# replay_adapter.net
KiCad netlist of a schematic drawn in EAGLE
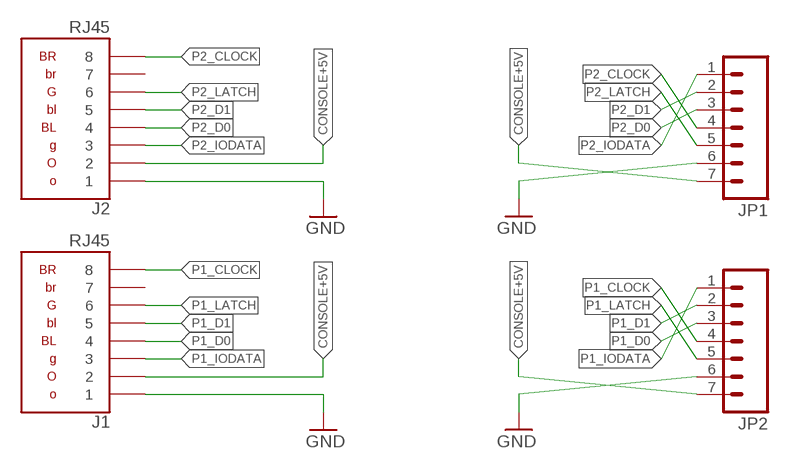
[diagram p0: schematic, sheet 1]

(export (version "E")
  (design (tool "Eeschema 10.0.6"))
  (components
    (comp (ref "J1")
      (value "RJ45")
      (footprint "eagle-import:RJ45")
      (libsource (lib "eagle-import") (part "RJ45"))
    )
    (comp (ref "J2")
      (value "RJ45")
      (footprint "eagle-import:RJ45")
      (libsource (lib "eagle-import") (part "RJ45"))
    )
    (comp (ref "JP1")
      (value "M07")
      (footprint "eagle-import:1X07")
      (libsource (lib "eagle-import") (part "M07"))
    )
    (comp (ref "JP2")
      (value "M07")
      (footprint "eagle-import:1X07")
      (libsource (lib "eagle-import") (part "M07"))
    )
  )
  (nets
    (net (code "1") (name "CONSOLE+5V") (class "Default")
      (node (ref "J1") (pin "2") (pinfunction "2_2") (pintype "bidirectional"))
      (node (ref "J2") (pin "2") (pinfunction "2_2") (pintype "bidirectional"))
      (node (ref "JP1") (pin "7") (pinfunction "7_7") (pintype "passive"))
      (node (ref "JP2") (pin "7") (pinfunction "7_7") (pintype "passive"))
    )
    (net (code "2") (name "GND") (class "Default")
      (node (ref "J1") (pin "1") (pinfunction "1_1") (pintype "bidirectional"))
      (node (ref "J2") (pin "1") (pinfunction "1_1") (pintype "bidirectional"))
      (node (ref "JP1") (pin "6") (pinfunction "6_6") (pintype "passive"))
      (node (ref "JP2") (pin "6") (pinfunction "6_6") (pintype "passive"))
    )
    (net (code "3") (name "P1_CLOCK") (class "Default")
      (node (ref "J1") (pin "8") (pinfunction "8_8") (pintype "bidirectional"))
      (node (ref "JP2") (pin "4") (pinfunction "4_4") (pintype "passive"))
    )
    (net (code "4") (name "P1_D0") (class "Default")
      (node (ref "J1") (pin "4") (pinfunction "4_4") (pintype "bidirectional"))
      (node (ref "JP2") (pin "3") (pinfunction "3_3") (pintype "passive"))
    )
    (net (code "5") (name "P1_D1") (class "Default")
      (node (ref "J1") (pin "5") (pinfunction "5_5") (pintype "bidirectional"))
      (node (ref "JP2") (pin "2") (pinfunction "2_2") (pintype "passive"))
    )
    (net (code "6") (name "P1_IODATA") (class "Default")
      (node (ref "J1") (pin "3") (pinfunction "3_3") (pintype "bidirectional"))
      (node (ref "JP2") (pin "1") (pinfunction "1_1") (pintype "passive"))
    )
    (net (code "7") (name "P1_LATCH") (class "Default")
      (node (ref "J1") (pin "6") (pinfunction "6_6") (pintype "bidirectional"))
      (node (ref "JP2") (pin "5") (pinfunction "5_5") (pintype "passive"))
    )
    (net (code "8") (name "P2_CLOCK") (class "Default")
      (node (ref "J2") (pin "8") (pinfunction "8_8") (pintype "bidirectional"))
      (node (ref "JP1") (pin "4") (pinfunction "4_4") (pintype "passive"))
    )
    (net (code "9") (name "P2_D0") (class "Default")
      (node (ref "J2") (pin "4") (pinfunction "4_4") (pintype "bidirectional"))
      (node (ref "JP1") (pin "3") (pinfunction "3_3") (pintype "passive"))
    )
    (net (code "10") (name "P2_D1") (class "Default")
      (node (ref "J2") (pin "5") (pinfunction "5_5") (pintype "bidirectional"))
      (node (ref "JP1") (pin "2") (pinfunction "2_2") (pintype "passive"))
    )
    (net (code "11") (name "P2_IODATA") (class "Default")
      (node (ref "J2") (pin "3") (pinfunction "3_3") (pintype "bidirectional"))
      (node (ref "JP1") (pin "1") (pinfunction "1_1") (pintype "passive"))
    )
    (net (code "12") (name "P2_LATCH") (class "Default")
      (node (ref "J2") (pin "6") (pinfunction "6_6") (pintype "bidirectional"))
      (node (ref "JP1") (pin "5") (pinfunction "5_5") (pintype "passive"))
    )
    (net (code "13") (name "unconnected-(J1-Pad7)") (class "Default")
      (node (ref "J1") (pin "7") (pinfunction "7_7") (pintype "bidirectional"))
    )
    (net (code "14") (name "unconnected-(J2-Pad7)") (class "Default")
      (node (ref "J2") (pin "7") (pinfunction "7_7") (pintype "bidirectional"))
    )
  )
)
